# gedge.net
KiCad netlist of a schematic drawn in EAGLE
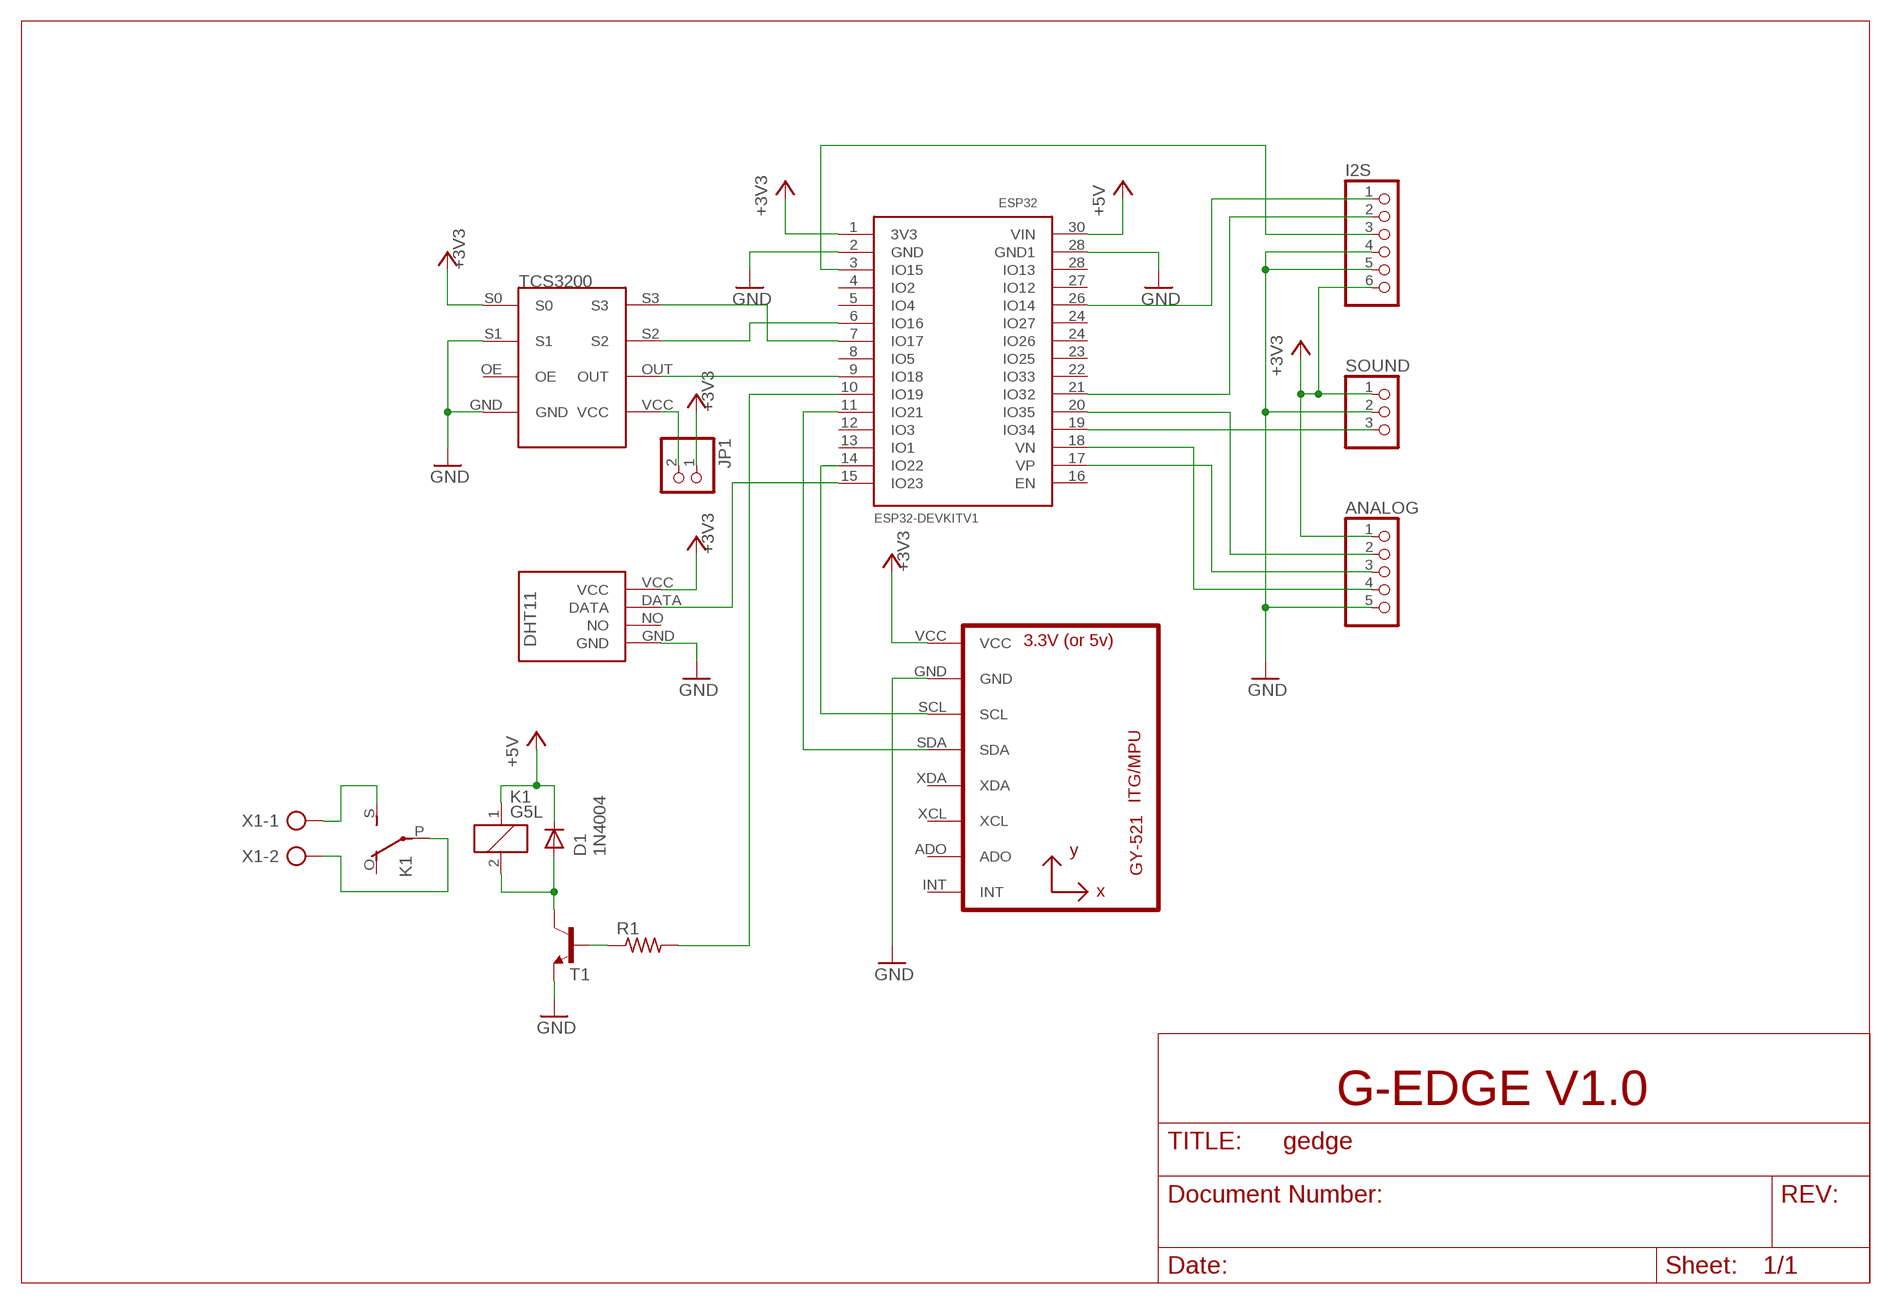
[diagram p0: schematic, sheet 1]

(export (version "E")
  (design (tool "Eeschema 10.0.6"))
  (components
    (comp (ref "ANALOG")
      (value "PINHD-1X5")
      (footprint "eagle-import:1X05")
      (libsource (lib "eagle-import") (part "PINHD-1X5"))
    )
    (comp (ref "D1")
      (value "1N4004")
      (footprint "eagle-import:DO41-10")
      (libsource (lib "eagle-import") (part "1N4004"))
    )
    (comp (ref "ESP32")
      (value "ESP32DEVKITV1")
      (footprint "eagle-import:ESP32-DEVKITV1")
      (libsource (lib "eagle-import") (part "ESP32DEVKITV1"))
    )
    (comp (ref "I2S")
      (value "PINHD-1X6")
      (footprint "eagle-import:1X06")
      (libsource (lib "eagle-import") (part "PINHD-1X6"))
    )
    (comp (ref "JP1")
      (value "PINHD-1X2")
      (footprint "eagle-import:1X02")
      (libsource (lib "eagle-import") (part "PINHD-1X2"))
    )
    (comp (ref "K1")
      (value "G5L")
      (footprint "eagle-import:G5LE")
      (libsource (lib "eagle-import") (part "G5L"))
    )
    (comp (ref "R1")
      (value "R-US_0204/7")
      (footprint "eagle-import:0204_7")
      (libsource (lib "eagle-import") (part "R-US_0204/7"))
    )
    (comp (ref "SOUND")
      (value "PINHD-1X3")
      (footprint "eagle-import:1X03")
      (libsource (lib "eagle-import") (part "PINHD-1X3"))
    )
    (comp (ref "T1")
      (value "BC107A-NPN-TO18-EBC")
      (footprint "eagle-import:TO18")
      (libsource (lib "eagle-import") (part "-NPN-TO18-EBCBC107A"))
    )
    (comp (ref "TCS3200")
      (value "TCS3200")
      (footprint "eagle-import:TCS3200")
      (libsource (lib "eagle-import") (part "TCS3200"))
    )
    (comp (ref "U$2")
      (value "DHT11")
      (footprint "eagle-import:DHT11")
      (libsource (lib "eagle-import") (part "DHT11"))
    )
    (comp (ref "U1")
      (value "GY-521MPU6050")
      (footprint "eagle-import:GY-521")
      (libsource (lib "eagle-import") (part "GY-521MPU6050"))
    )
    (comp (ref "X1")
      (value "AK500/2")
      (footprint "eagle-import:AK500_2")
      (libsource (lib "eagle-import") (part "AK500/2"))
    )
  )
  (nets
    (net (code "1") (name "+3V3") (class "Default")
      (node (ref "ANALOG") (pin "1") (pinfunction "1_1") (pintype "passive"))
      (node (ref "ESP32") (pin "1") (pinfunction "3V3_1") (pintype "bidirectional"))
      (node (ref "I2S") (pin "6") (pinfunction "6_6") (pintype "passive"))
      (node (ref "JP1") (pin "1") (pinfunction "1_1") (pintype "passive"))
      (node (ref "SOUND") (pin "1") (pinfunction "1_1") (pintype "passive"))
      (node (ref "TCS3200") (pin "S0") (pinfunction "S0_S0") (pintype "bidirectional"))
      (node (ref "U$2") (pin "VCC") (pinfunction "VCC_VCC") (pintype "bidirectional"))
      (node (ref "U1") (pin "VCC") (pinfunction "VCC_VCC") (pintype "bidirectional"))
    )
    (net (code "2") (name "+5V") (class "Default")
      (node (ref "D1") (pin "C") (pinfunction "C_C") (pintype "passive"))
      (node (ref "ESP32") (pin "30") (pinfunction "VIN_30") (pintype "bidirectional"))
      (node (ref "K1") (pin "1") (pinfunction "1_1") (pintype "passive"))
    )
    (net (code "3") (name "GND") (class "Default")
      (node (ref "ANALOG") (pin "5") (pinfunction "5_5") (pintype "passive"))
      (node (ref "ESP32") (pin "2") (pinfunction "GND_2") (pintype "bidirectional"))
      (node (ref "ESP32") (pin "28") (pinfunction "GND1_28") (pintype "bidirectional"))
      (node (ref "I2S") (pin "4") (pinfunction "4_4") (pintype "passive"))
      (node (ref "I2S") (pin "5") (pinfunction "5_5") (pintype "passive"))
      (node (ref "SOUND") (pin "2") (pinfunction "2_2") (pintype "passive"))
      (node (ref "T1") (pin "1") (pinfunction "E_1") (pintype "passive"))
      (node (ref "TCS3200") (pin "GND") (pinfunction "GND_GND") (pintype "bidirectional"))
      (node (ref "TCS3200") (pin "S1") (pinfunction "S1_S1") (pintype "bidirectional"))
      (node (ref "U$2") (pin "GND") (pinfunction "GND_GND") (pintype "bidirectional"))
      (node (ref "U1") (pin "GND") (pinfunction "GND_GND") (pintype "bidirectional"))
    )
    (net (code "4") (name "Net-(ESP32-IO14)") (class "Default")
      (node (ref "ESP32") (pin "26") (pinfunction "IO14_26") (pintype "bidirectional"))
      (node (ref "I2S") (pin "1") (pinfunction "1_1") (pintype "passive"))
    )
    (net (code "5") (name "Net-(ESP32-IO15)") (class "Default")
      (node (ref "ESP32") (pin "3") (pinfunction "IO15_3") (pintype "bidirectional"))
      (node (ref "I2S") (pin "3") (pinfunction "3_3") (pintype "passive"))
    )
    (net (code "6") (name "Net-(ESP32-IO16)") (class "Default")
      (node (ref "ESP32") (pin "6") (pinfunction "IO16_6") (pintype "bidirectional"))
      (node (ref "TCS3200") (pin "S2") (pinfunction "S2_S2") (pintype "bidirectional"))
    )
    (net (code "7") (name "Net-(ESP32-IO17)") (class "Default")
      (node (ref "ESP32") (pin "7") (pinfunction "IO17_7") (pintype "bidirectional"))
      (node (ref "TCS3200") (pin "S3") (pinfunction "S3_S3") (pintype "bidirectional"))
    )
    (net (code "8") (name "Net-(ESP32-IO18)") (class "Default")
      (node (ref "ESP32") (pin "9") (pinfunction "IO18_9") (pintype "bidirectional"))
      (node (ref "TCS3200") (pin "OUT") (pinfunction "OUT_OUT") (pintype "bidirectional"))
    )
    (net (code "9") (name "Net-(ESP32-IO19)") (class "Default")
      (node (ref "ESP32") (pin "10") (pinfunction "IO19_10") (pintype "bidirectional"))
      (node (ref "R1") (pin "2") (pinfunction "2_2") (pintype "passive"))
    )
    (net (code "10") (name "Net-(ESP32-IO21)") (class "Default")
      (node (ref "ESP32") (pin "11") (pinfunction "IO21_11") (pintype "bidirectional"))
      (node (ref "U1") (pin "SDA") (pinfunction "SDA_SDA") (pintype "bidirectional"))
    )
    (net (code "11") (name "Net-(ESP32-IO22)") (class "Default")
      (node (ref "ESP32") (pin "14") (pinfunction "IO22_14") (pintype "bidirectional"))
      (node (ref "U1") (pin "SCL") (pinfunction "SCL_SCL") (pintype "bidirectional"))
    )
    (net (code "12") (name "Net-(ESP32-IO23)") (class "Default")
      (node (ref "ESP32") (pin "15") (pinfunction "IO23_15") (pintype "bidirectional"))
      (node (ref "U$2") (pin "DATA") (pinfunction "DATA_DATA") (pintype "bidirectional"))
    )
    (net (code "13") (name "Net-(ESP32-IO32)") (class "Default")
      (node (ref "ESP32") (pin "21") (pinfunction "IO32_21") (pintype "bidirectional"))
      (node (ref "I2S") (pin "2") (pinfunction "2_2") (pintype "passive"))
    )
    (net (code "14") (name "Net-(ESP32-IO34)") (class "Default")
      (node (ref "ESP32") (pin "19") (pinfunction "IO34_19") (pintype "bidirectional"))
      (node (ref "SOUND") (pin "3") (pinfunction "3_3") (pintype "passive"))
    )
    (net (code "15") (name "Net-(ESP32-IO35)") (class "Default")
      (node (ref "ANALOG") (pin "2") (pinfunction "2_2") (pintype "passive"))
      (node (ref "ESP32") (pin "20") (pinfunction "IO35_20") (pintype "bidirectional"))
    )
    (net (code "16") (name "Net-(ESP32-VN)") (class "Default")
      (node (ref "ANALOG") (pin "4") (pinfunction "4_4") (pintype "passive"))
      (node (ref "ESP32") (pin "18") (pinfunction "VN_18") (pintype "bidirectional"))
    )
    (net (code "17") (name "Net-(ESP32-VP)") (class "Default")
      (node (ref "ANALOG") (pin "3") (pinfunction "3_3") (pintype "passive"))
      (node (ref "ESP32") (pin "17") (pinfunction "VP_17") (pintype "bidirectional"))
    )
    (net (code "18") (name "Net-(JP1-Pad2)") (class "Default")
      (node (ref "JP1") (pin "2") (pinfunction "2_2") (pintype "passive"))
      (node (ref "TCS3200") (pin "VCC") (pinfunction "VCC_VCC") (pintype "bidirectional"))
    )
    (net (code "19") (name "Net-(T1-B)") (class "Default")
      (node (ref "R1") (pin "1") (pinfunction "1_1") (pintype "passive"))
      (node (ref "T1") (pin "2") (pinfunction "B_2") (pintype "passive"))
    )
    (net (code "20") (name "Net-(T1-C)") (class "Default")
      (node (ref "D1") (pin "A") (pinfunction "A_A") (pintype "passive"))
      (node (ref "K1") (pin "2") (pinfunction "2_2") (pintype "passive"))
      (node (ref "T1") (pin "3") (pinfunction "C_3") (pintype "passive"))
    )
    (net (code "21") (name "Net-(X1A-KL)") (class "Default")
      (node (ref "K1") (pin "S") (pinfunction "S_S") (pintype "passive"))
      (node (ref "X1") (pin "1") (pinfunction "KL_1") (pintype "passive"))
    )
    (net (code "22") (name "Net-(X1B-KL)") (class "Default")
      (node (ref "K1") (pin "P") (pinfunction "P_P") (pintype "passive"))
      (node (ref "X1") (pin "2") (pinfunction "KL_2") (pintype "passive"))
    )
    (net (code "23") (name "unconnected-(ESP32-EN-Pad16)") (class "Default")
      (node (ref "ESP32") (pin "16") (pinfunction "EN_16") (pintype "bidirectional"))
    )
    (net (code "24") (name "unconnected-(ESP32-IO1-Pad13)") (class "Default")
      (node (ref "ESP32") (pin "13") (pinfunction "IO1_13") (pintype "bidirectional"))
    )
    (net (code "25") (name "unconnected-(ESP32-IO2-Pad4)") (class "Default")
      (node (ref "ESP32") (pin "4") (pinfunction "IO2_4") (pintype "bidirectional"))
    )
    (net (code "26") (name "unconnected-(ESP32-IO3-Pad12)") (class "Default")
      (node (ref "ESP32") (pin "12") (pinfunction "IO3_12") (pintype "bidirectional"))
    )
    (net (code "27") (name "unconnected-(ESP32-IO4-Pad5)") (class "Default")
      (node (ref "ESP32") (pin "5") (pinfunction "IO4_5") (pintype "bidirectional"))
    )
    (net (code "28") (name "unconnected-(ESP32-IO5-Pad8)") (class "Default")
      (node (ref "ESP32") (pin "8") (pinfunction "IO5_8") (pintype "bidirectional"))
    )
    (net (code "29") (name "unconnected-(ESP32-IO12-Pad27)") (class "Default")
      (node (ref "ESP32") (pin "27") (pinfunction "IO12_27") (pintype "bidirectional"))
    )
    (net (code "30") (name "unconnected-(ESP32-IO13-Pad28)") (class "Default")
      (node (ref "ESP32") (pin "28") (pinfunction "IO13_28") (pintype "bidirectional"))
    )
    (net (code "31") (name "unconnected-(ESP32-IO25-Pad23)") (class "Default")
      (node (ref "ESP32") (pin "23") (pinfunction "IO25_23") (pintype "bidirectional"))
    )
    (net (code "32") (name "unconnected-(ESP32-IO26-Pad24)") (class "Default")
      (node (ref "ESP32") (pin "24") (pinfunction "IO26_24") (pintype "bidirectional"))
    )
    (net (code "33") (name "unconnected-(ESP32-IO27-Pad24)") (class "Default")
      (node (ref "ESP32") (pin "24") (pinfunction "IO27_24") (pintype "bidirectional"))
    )
    (net (code "34") (name "unconnected-(ESP32-IO33-Pad22)") (class "Default")
      (node (ref "ESP32") (pin "22") (pinfunction "IO33_22") (pintype "bidirectional"))
    )
    (net (code "35") (name "unconnected-(K1-PadO)") (class "Default")
      (node (ref "K1") (pin "O") (pinfunction "O_O") (pintype "passive"))
    )
    (net (code "36") (name "unconnected-(TCS3200-PadOE)") (class "Default")
      (node (ref "TCS3200") (pin "OE") (pinfunction "OE_OE") (pintype "bidirectional"))
    )
    (net (code "37") (name "unconnected-(U$2-PadNO)") (class "Default")
      (node (ref "U$2") (pin "NO") (pinfunction "NO_NO") (pintype "bidirectional"))
    )
    (net (code "38") (name "unconnected-(U1-PadADO)") (class "Default")
      (node (ref "U1") (pin "ADO") (pinfunction "ADO_ADO") (pintype "bidirectional"))
    )
    (net (code "39") (name "unconnected-(U1-PadINT)") (class "Default")
      (node (ref "U1") (pin "INT") (pinfunction "INT_INT") (pintype "bidirectional"))
    )
    (net (code "40") (name "unconnected-(U1-PadXCL)") (class "Default")
      (node (ref "U1") (pin "XCL") (pinfunction "XCL_XCL") (pintype "bidirectional"))
    )
    (net (code "41") (name "unconnected-(U1-PadXDA)") (class "Default")
      (node (ref "U1") (pin "XDA") (pinfunction "XDA_XDA") (pintype "bidirectional"))
    )
  )
)
